# Motor.net
KiCad netlist of a schematic drawn in Altium Designer
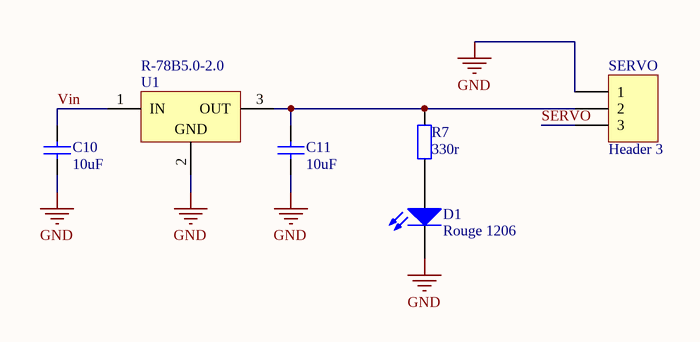
[diagram p0: Motor.SchDoc]

(export (version "E")
  (design (tool "Eeschema 10.0.6"))
  (components
    (comp (ref "C10")
      (value "10uF")
      (footprint "1206-C")
      (description "Condensateur céramique multicouche CMS, 10 µF, 25 V, 1206 [3216 Metric], ± 10%, X5R, Série MC")
      (fields (field (name "VOLTAGE") "25V"))
      (libsource (lib "MGLib_v2") (part "Cap_np"))
    )
    (comp (ref "C11")
      (value "10uF")
      (footprint "1206-C")
      (description "Condensateur céramique multicouche CMS, 10 µF, 25 V, 1206 [3216 Metric], ± 10%, X5R, Série MC")
      (fields (field (name "VOLTAGE") "25V"))
      (libsource (lib "MGLib_v2") (part "Cap_np"))
    )
    (comp (ref "D1")
      (value "Rouge 1206")
      (footprint "1206-Led-R")
      (description "LED, Basse puissance, Rouge, CMS, 1206 (Métrique 3216), 20 mA, 1.85 V, 640 nm")
      (fields (field (name "VOLTAGE") "1.85V"))
      (libsource (lib "MGLib_v2") (part "LED CMS 1206 Red"))
    )
    (comp (ref "R7")
      (value "330r")
      (footprint "0805-R")
      (description "Résistance à puce CMS, Couche épaisse, 330 ohm, ± 1%, 125 mW, 0805 [2012 Metric], Couche épaisse")
      (fields (field (name "VOLTAGE") "150V"))
      (libsource (lib "MGLib_v2") (part "Res"))
    )
    (comp (ref "SERVO")
      (value "Header 3")
      (footprint "HDR1X3")
      (description "Header mâle, Carte-à-carte, 2.54 mm, 1 Rangée(s), 10 Contact(s), Traversant, droit, Série 2211S")
      (libsource (lib "Miscellaneous Connectors") (part "Header 3"))
    )
    (comp (ref "U1")
      (value "R-78B5.0-2.0")
      (footprint "R78HB50V")
      (description "Convertisseur DC/DC POL non isolé, 1 sortie, 10 W, 5 V, 2 A, Fixe, Traversant")
      (fields (field (name "VOLTAGE") "IN 6.5V-32V ; OUT 5V"))
      (libsource (lib "MGLib_v2") (part "R78HB50"))
    )
  )
  (nets
    (net (code "1") (name "/SERVO") (class "Default")
      (node (ref "SERVO") (pin "3") (pinfunction "3_3") (pintype "passive"))
    )
    (net (code "2") (name "/Vin") (class "Default")
      (node (ref "C10") (pin "2") (pinfunction "2_2") (pintype "passive"))
      (node (ref "U1") (pin "1") (pinfunction "IN_1") (pintype "passive"))
    )
    (net (code "3") (name "GND") (class "Default")
      (node (ref "C10") (pin "1") (pinfunction "1_1") (pintype "passive"))
      (node (ref "C11") (pin "1") (pinfunction "1_1") (pintype "passive"))
      (node (ref "D1") (pin "1") (pinfunction "K_1") (pintype "passive"))
      (node (ref "SERVO") (pin "1") (pinfunction "1_1") (pintype "passive"))
      (node (ref "U1") (pin "2") (pinfunction "GND_2") (pintype "passive"))
    )
    (net (code "4") (name "Net-(D1-A)") (class "Default")
      (node (ref "D1") (pin "2") (pinfunction "A_2") (pintype "passive"))
      (node (ref "R7") (pin "1") (pinfunction "1_1") (pintype "passive"))
    )
    (net (code "5") (name "Net-(U1-OUT)") (class "Default")
      (node (ref "C11") (pin "2") (pinfunction "2_2") (pintype "passive"))
      (node (ref "R7") (pin "2") (pinfunction "2_2") (pintype "passive"))
      (node (ref "SERVO") (pin "2") (pinfunction "2_2") (pintype "passive"))
      (node (ref "U1") (pin "3") (pinfunction "OUT_3") (pintype "passive"))
    )
  )
)
